# Mergen_Ground_Station_V2_0.net
KiCad netlist of a schematic drawn in EAGLE
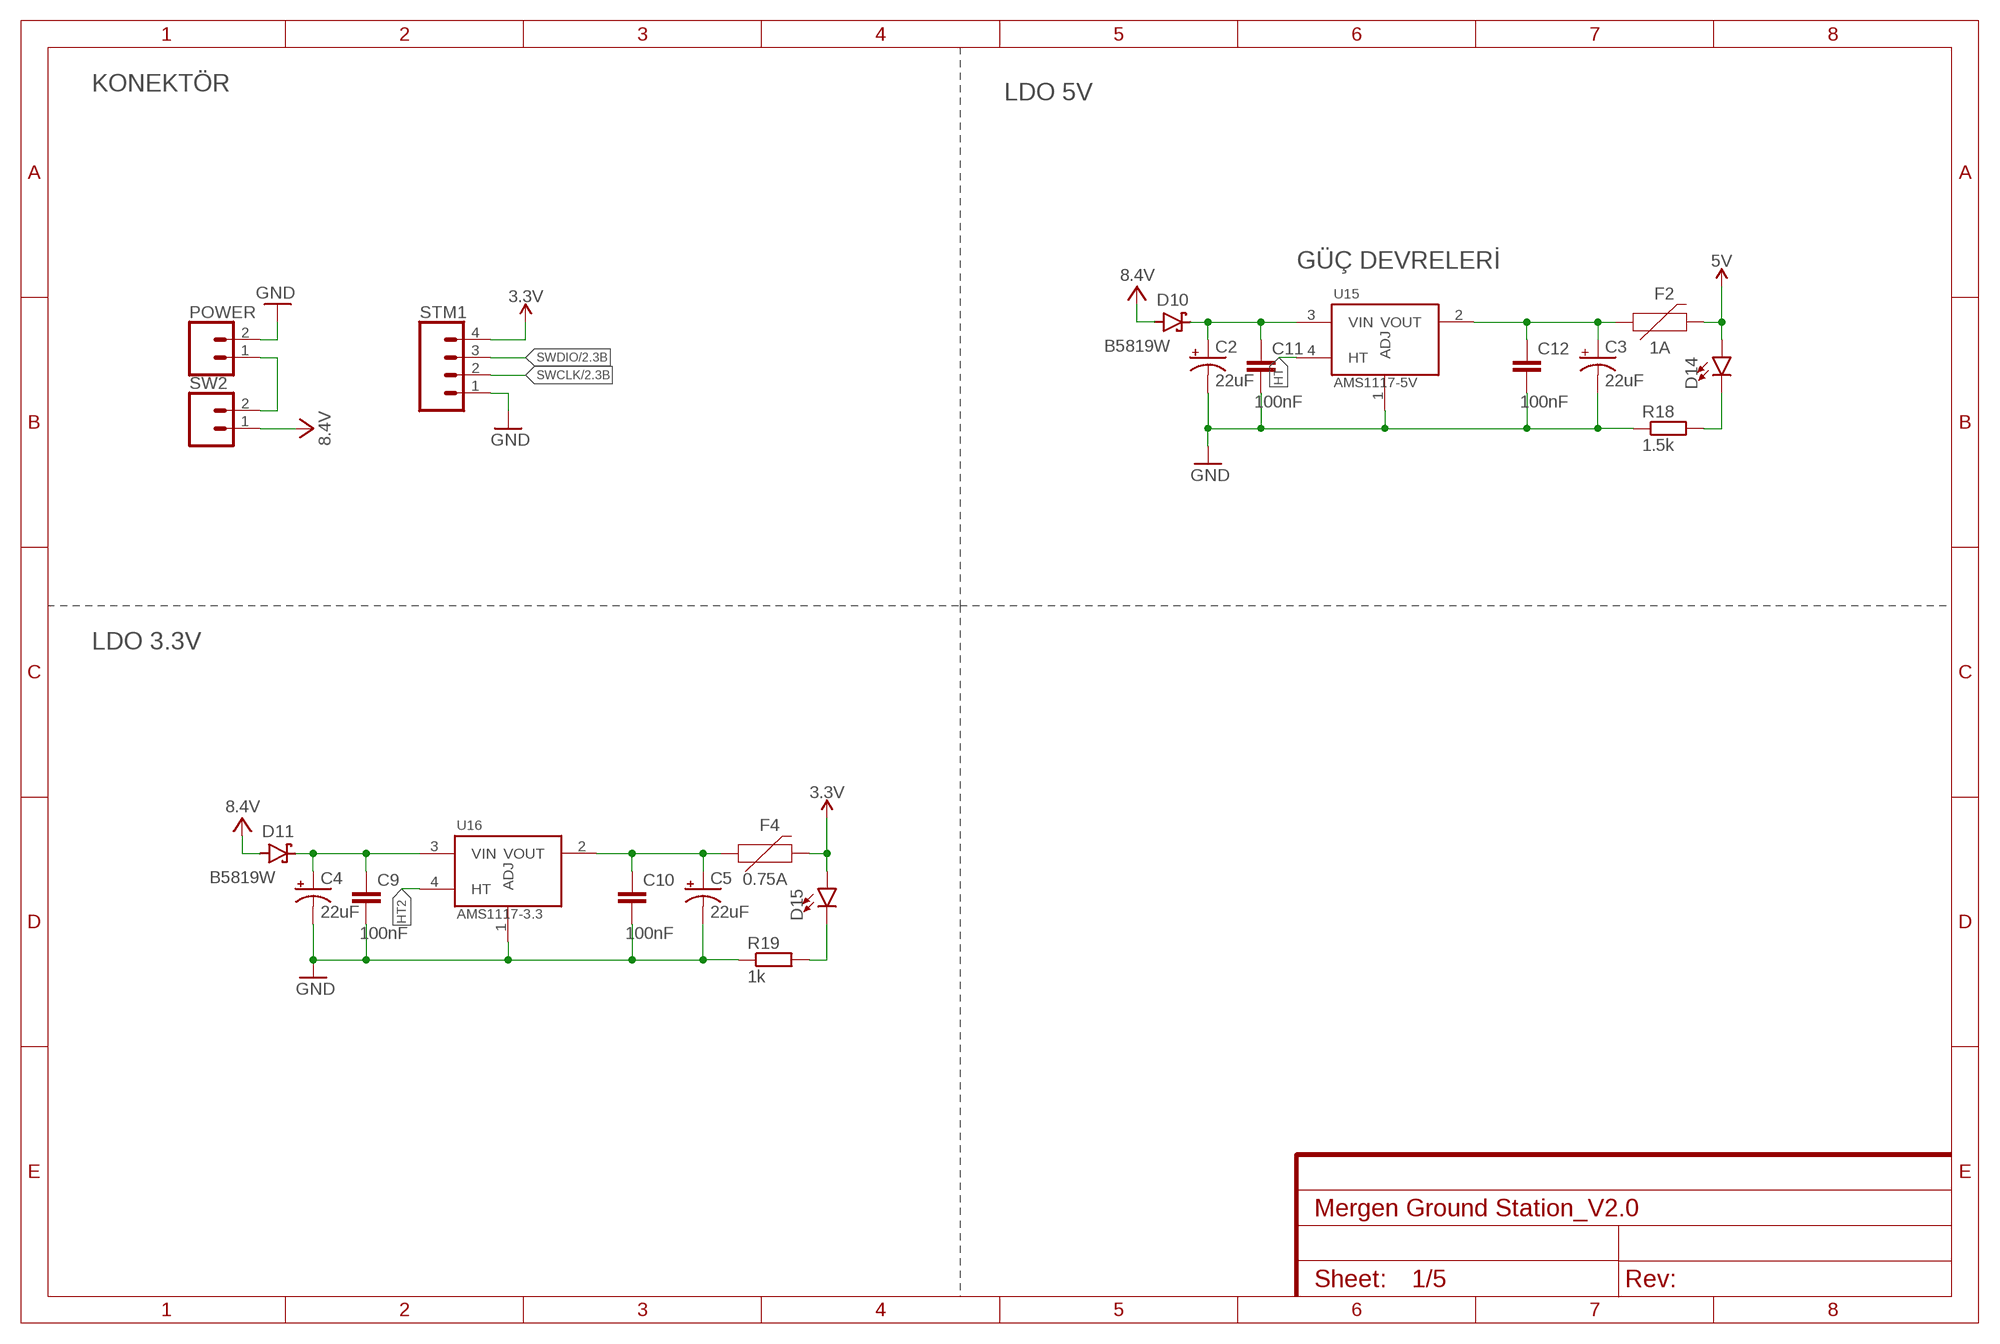
[diagram p0: schematic, sheet 1]
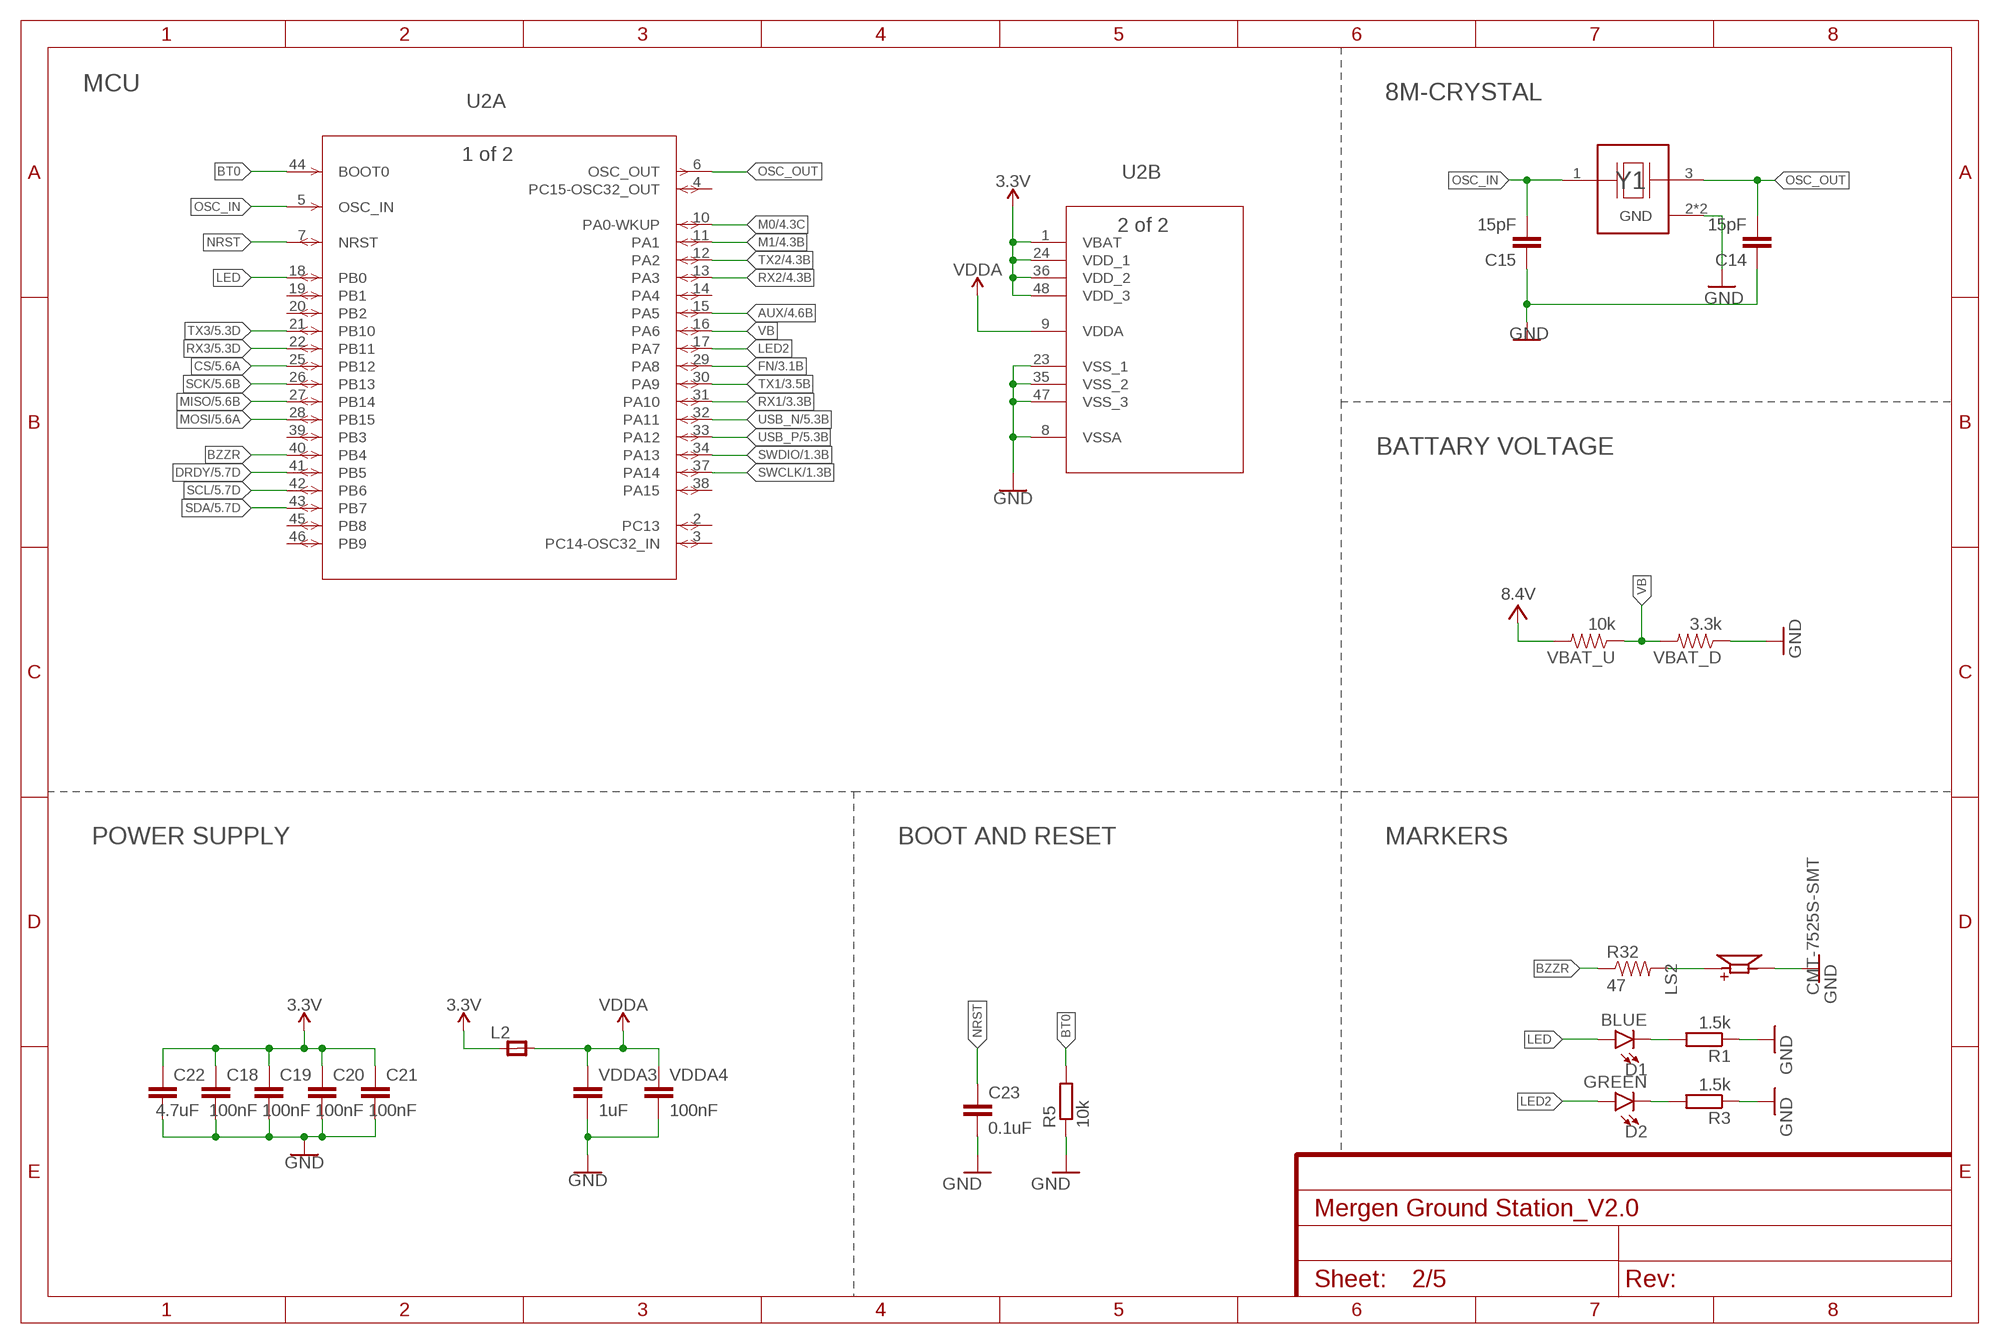
[diagram p1: schematic, sheet 2]
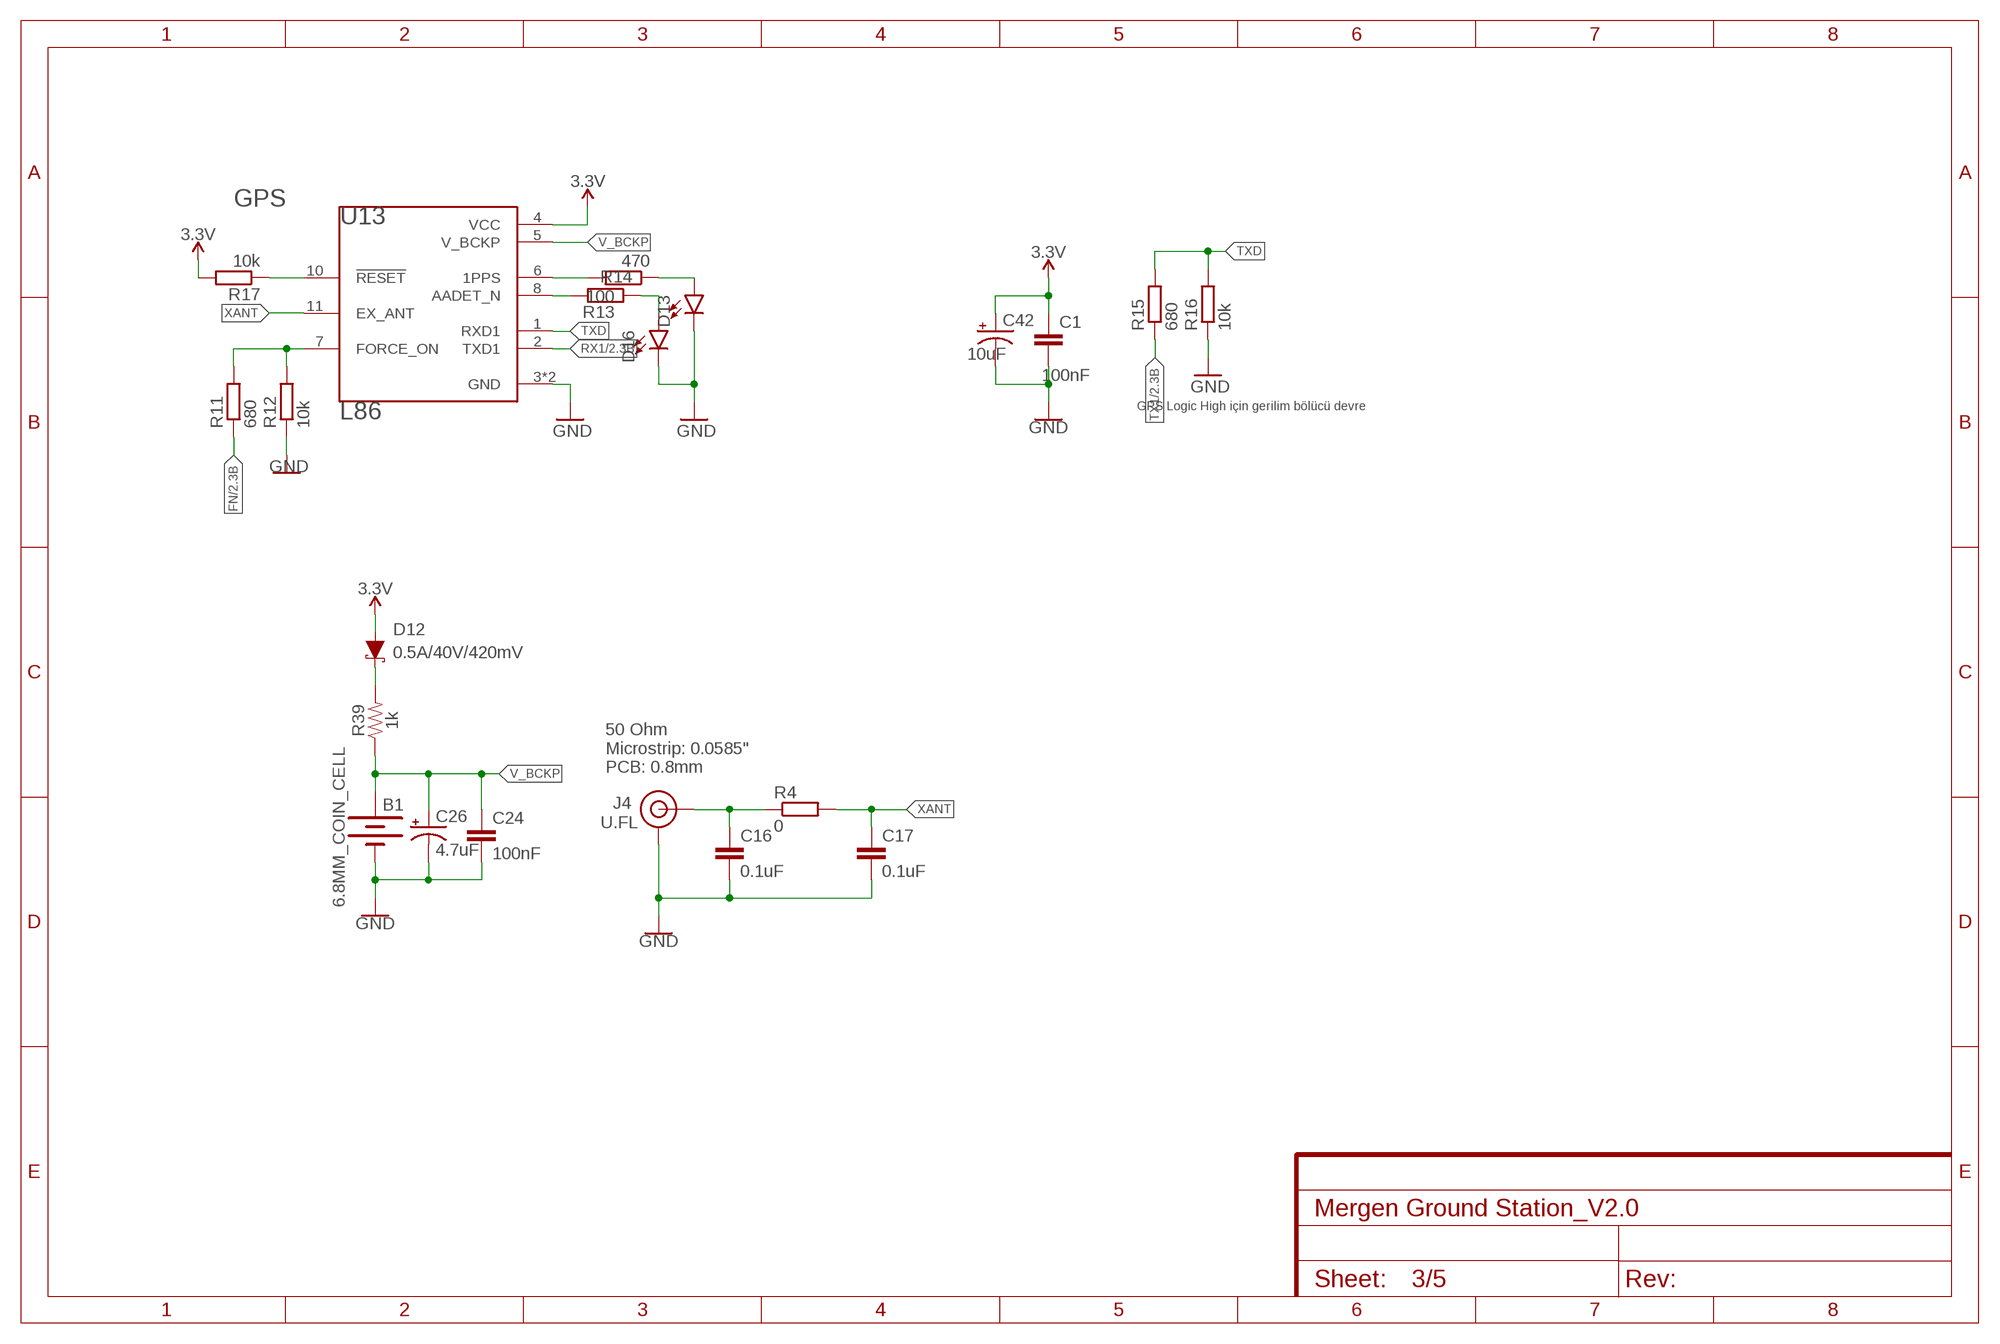
[diagram p2: schematic, sheet 3]
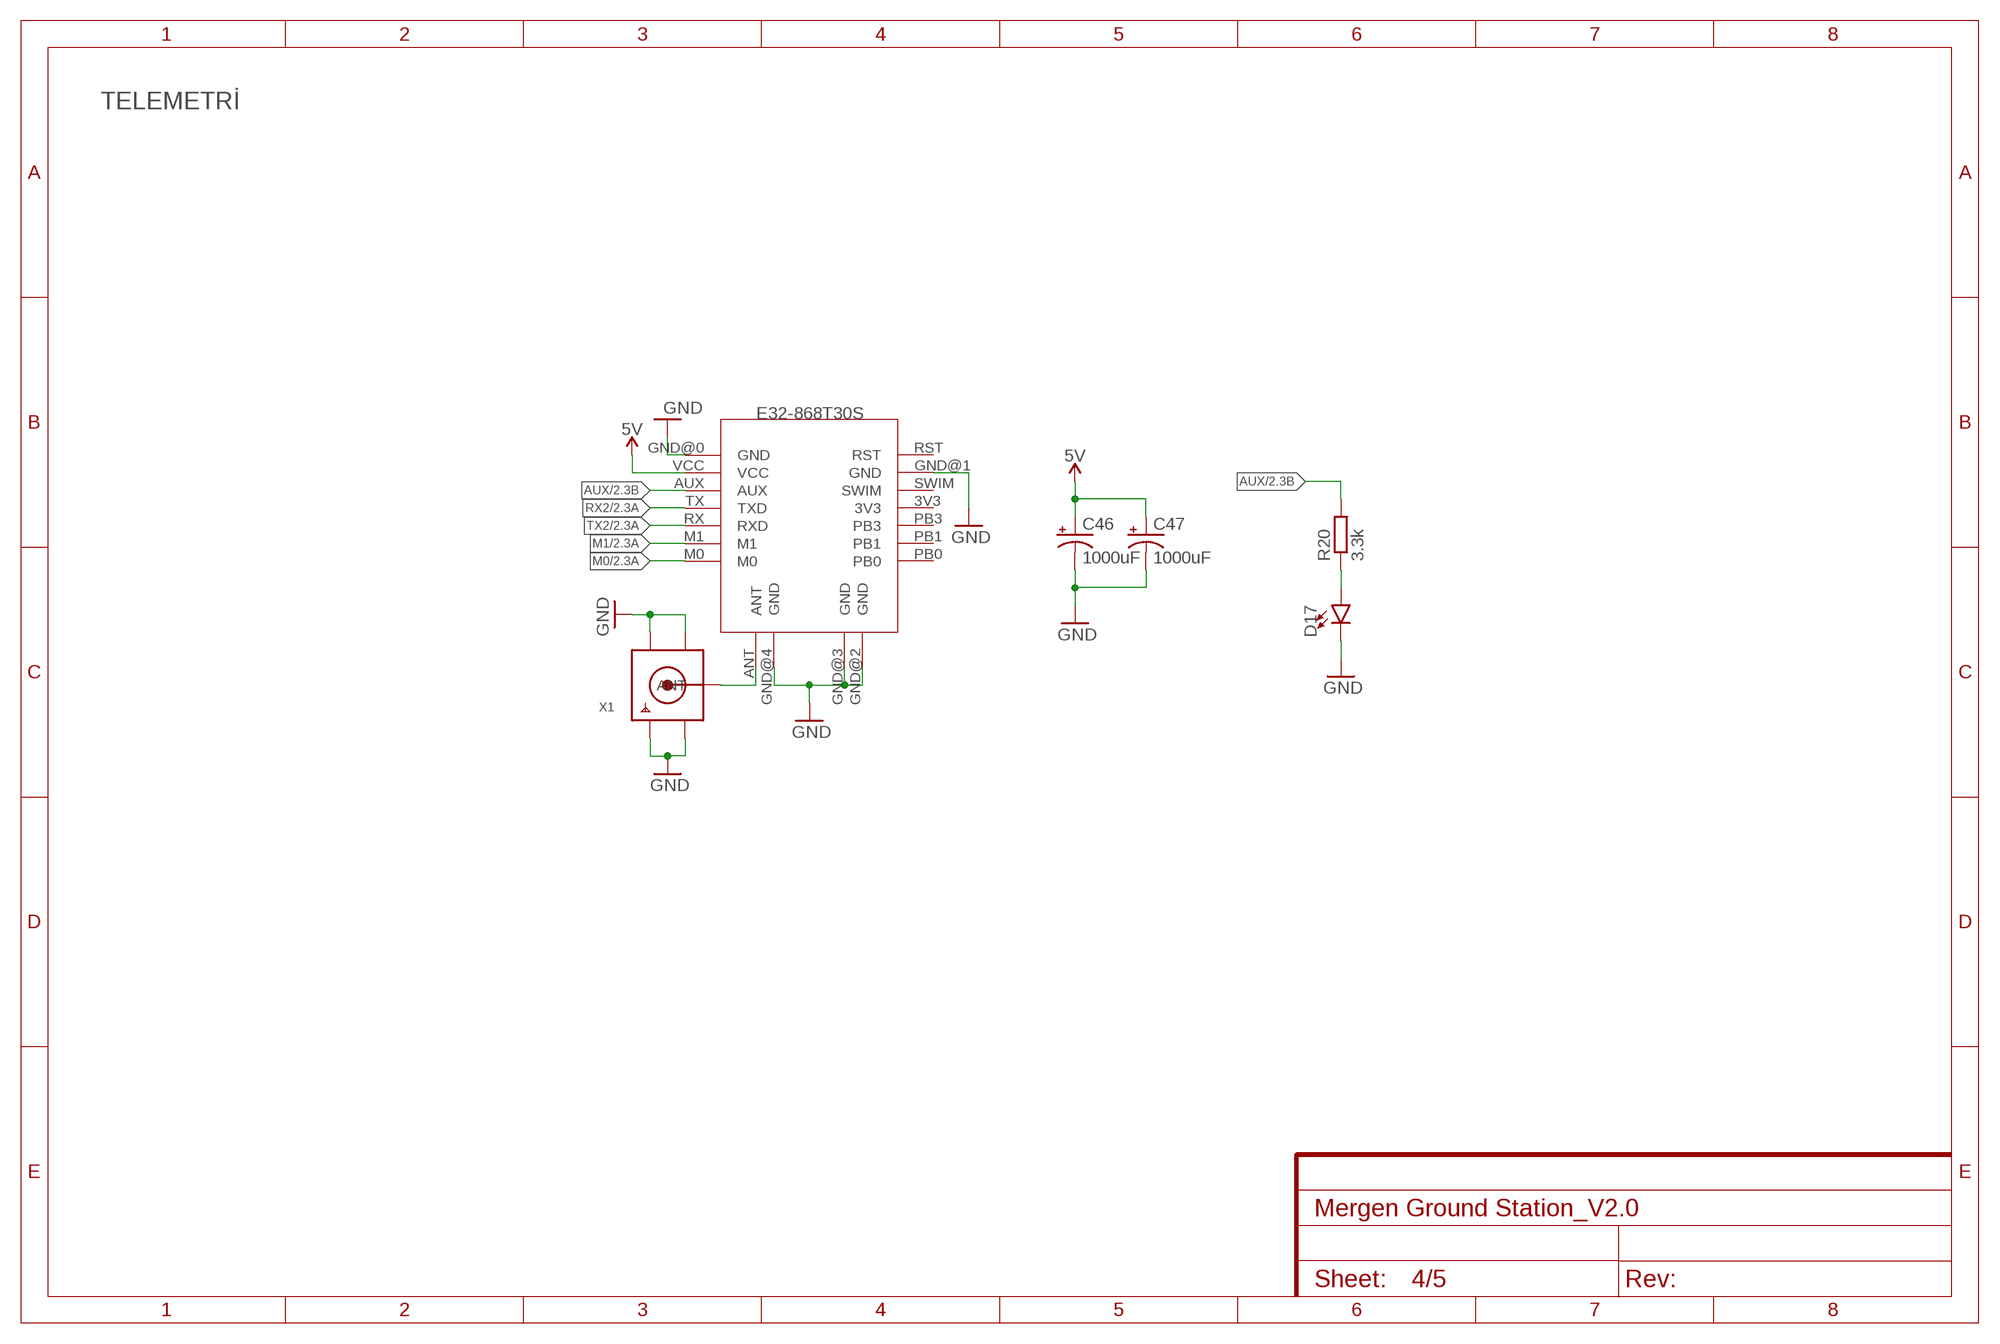
[diagram p3: schematic, sheet 4]
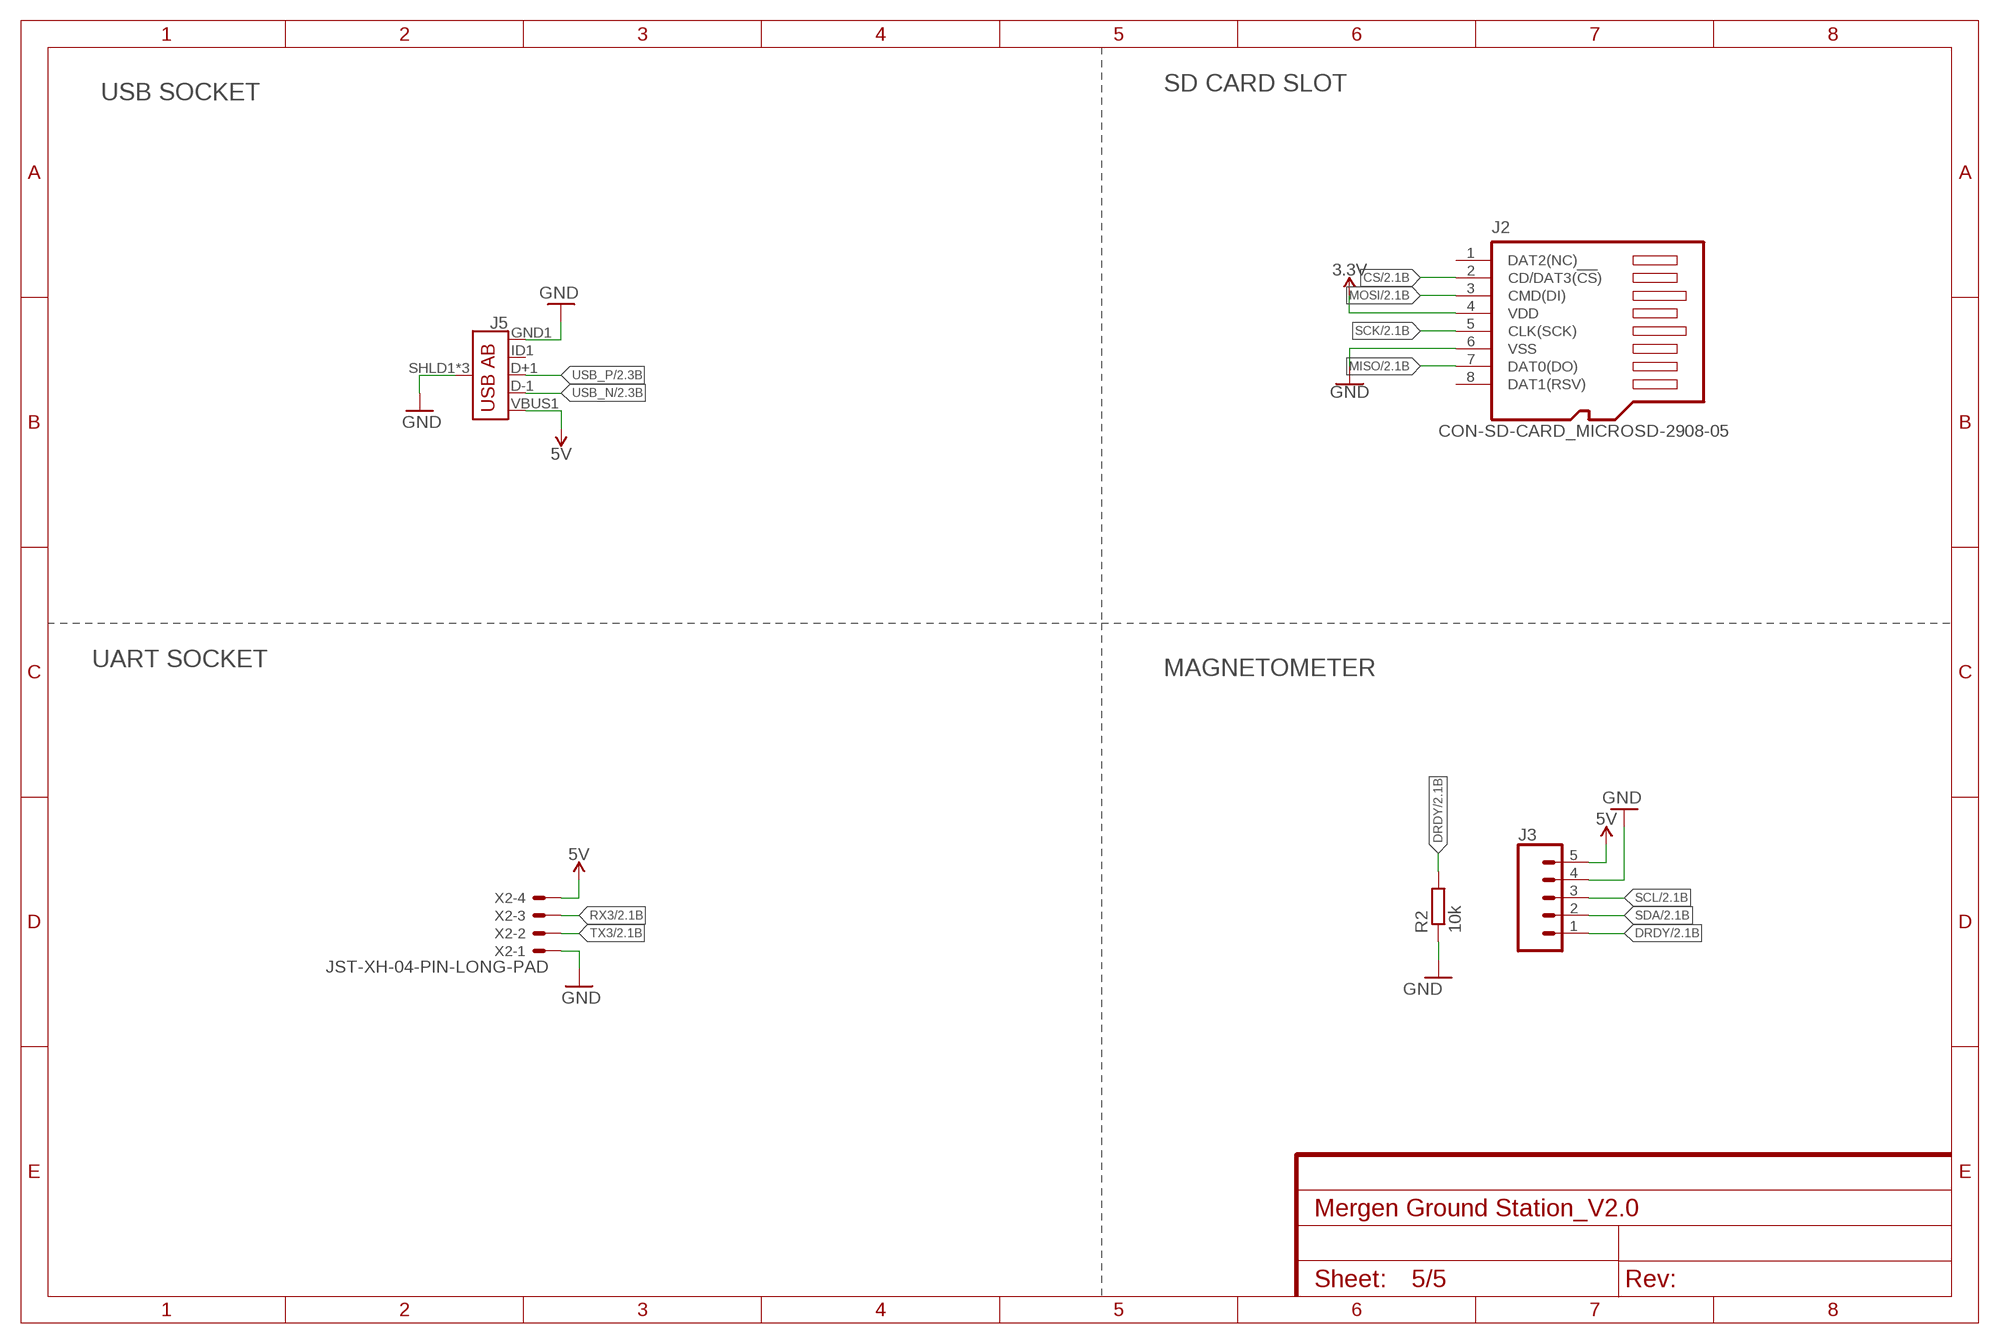
[diagram p4: schematic, sheet 5]

(export (version "E")
  (design (tool "Eeschema 10.0.6"))
  (components
    (comp (ref "B1")
      (value "6.8MM_COIN_CELL")
      (footprint "eagle-import:BATTCON-6.8MM")
      (libsource (lib "eagle-import") (part "BATTERY-6.8MM_SMD"))
    )
    (comp (ref "C1")
      (value "100nF")
      (footprint "eagle-import:C0603")
      (libsource (lib "eagle-import") (part "C-EUC0603"))
    )
    (comp (ref "C16")
      (value "0.1uF")
      (footprint "eagle-import:C0603")
      (libsource (lib "eagle-import") (part "C-EUC0603"))
    )
    (comp (ref "C17")
      (value "0.1uF")
      (footprint "eagle-import:C0603")
      (libsource (lib "eagle-import") (part "C-EUC0603"))
    )
    (comp (ref "C24")
      (value "100nF")
      (footprint "eagle-import:C0603")
      (libsource (lib "eagle-import") (part "C-EUC0603"))
    )
    (comp (ref "C26")
      (value "4.7uF")
      (footprint "eagle-import:A_3216-18R")
      (libsource (lib "eagle-import") (part "rcl_334_CPOL-USA/3216-18R"))
    )
    (comp (ref "C42")
      (value "10uF")
      (footprint "eagle-import:EIA3216")
      (libsource (lib "eagle-import") (part "10UF-POLAR-EIA3216-16V-10%(TANT)"))
    )
    (comp (ref "D12")
      (value "0.5A/40V/420mV")
      (footprint "eagle-import:SOD-323")
      (libsource (lib "eagle-import") (part "DIODE-SCHOTTKY-PMEG4005EJ"))
    )
    (comp (ref "D13")
      (value "LED0603")
      (footprint "eagle-import:LED-0603")
      (libsource (lib "eagle-import") (part "LED0603"))
    )
    (comp (ref "D16")
      (value "LED0603")
      (footprint "eagle-import:LED-0603")
      (libsource (lib "eagle-import") (part "LED0603"))
    )
    (comp (ref "J4")
      (value "U.FL")
      (footprint "eagle-import:U.FL")
      (libsource (lib "eagle-import") (part "U.FL2PIN"))
    )
    (comp (ref "R4")
      (value "0")
      (footprint "eagle-import:R0603")
      (libsource (lib "eagle-import") (part "R-EU_R0603"))
    )
    (comp (ref "R11")
      (value "680")
      (footprint "eagle-import:R0603")
      (libsource (lib "eagle-import") (part "R-EU_R0603"))
    )
    (comp (ref "R12")
      (value "10k")
      (footprint "eagle-import:R0603")
      (libsource (lib "eagle-import") (part "R-EU_R0603"))
    )
    (comp (ref "R13")
      (value "100")
      (footprint "eagle-import:R0603")
      (libsource (lib "eagle-import") (part "R-EU_R0603"))
    )
    (comp (ref "R14")
      (value "470")
      (footprint "eagle-import:R0603")
      (libsource (lib "eagle-import") (part "R-EU_R0603"))
    )
    (comp (ref "R15")
      (value "680")
      (footprint "eagle-import:R0603")
      (libsource (lib "eagle-import") (part "R-EU_R0603"))
    )
    (comp (ref "R16")
      (value "10k")
      (footprint "eagle-import:R0603")
      (libsource (lib "eagle-import") (part "R-EU_R0603"))
    )
    (comp (ref "R17")
      (value "10k")
      (footprint "eagle-import:R0603")
      (libsource (lib "eagle-import") (part "R-EU_R0603"))
    )
    (comp (ref "R39")
      (value "1k")
      (footprint "eagle-import:0603")
      (libsource (lib "eagle-import") (part "1KOHM-0603-1/10W-1%"))
    )
    (comp (ref "U13")
      (value "L86")
      (footprint "eagle-import:XCVR_L86")
      (fields (field (name "MF") "Quectel"))
      (libsource (lib "eagle-import") (part "L86"))
    )
    (comp (ref "C46")
      (value "1000uF")
      (footprint "eagle-import:150CLZ-1010")
      (libsource (lib "eagle-import") (part "CPOL-US150CLZ-1010"))
    )
    (comp (ref "C47")
      (value "1000uF")
      (footprint "eagle-import:150CLZ-1010")
      (libsource (lib "eagle-import") (part "CPOL-US150CLZ-1010"))
    )
    (comp (ref "D17")
      (value "LED0603")
      (footprint "eagle-import:LED-0603")
      (libsource (lib "eagle-import") (part "LED0603"))
    )
    (comp (ref "R20")
      (value "3.3k")
      (footprint "eagle-import:R0603")
      (libsource (lib "eagle-import") (part "R-EU_R0603"))
    )
    (comp (ref "U14")
      (value "E32-868T30S")
      (footprint "eagle-import:E32-868T30S")
      (libsource (lib "eagle-import") (part "E32-868T30S"))
    )
    (comp (ref "X1")
      (value "SMACONNECTOR")
      (footprint "eagle-import:SMA90_DIP")
      (libsource (lib "eagle-import") (part "SMACONNECTOR"))
    )
    (comp (ref "J2")
      (value "CON-SD-CARD_MICROSD-2908-05")
      (footprint "eagle-import:CON-SD-CARD_2908-05")
      (libsource (lib "eagle-import") (part "CON-SD-CARD_MICROSD-2908-05"))
    )
    (comp (ref "J3")
      (value "CONN_05LOCK_LONGPADS")
      (footprint "eagle-import:1X05_LOCK_LONGPADS")
      (libsource (lib "eagle-import") (part "CONN_05LOCK_LONGPADS"))
    )
    (comp (ref "J5")
      (value "USB_AB_SMT")
      (footprint "eagle-import:USB-AB-MICRO-SMD")
      (libsource (lib "eagle-import") (part "USB_AB_SMT"))
    )
    (comp (ref "R2")
      (value "10k")
      (footprint "eagle-import:R0603")
      (libsource (lib "eagle-import") (part "R-EU_R0603"))
    )
    (comp (ref "X2")
      (value "JST-XH-04-PIN-LONG-PAD")
      (footprint "eagle-import:JST-XH-04-PACKAGE-LONG-PAD")
      (libsource (lib "eagle-import") (part "JST-XH-04-PIN-LONG-PAD"))
    )
    (comp (ref "C2")
      (value "22uF")
      (footprint "eagle-import:CT3528")
      (libsource (lib "eagle-import") (part "rcl_334_CPOL-USCT3528"))
    )
    (comp (ref "C3")
      (value "22uF")
      (footprint "eagle-import:CT3528")
      (libsource (lib "eagle-import") (part "rcl_334_CPOL-USCT3528"))
    )
    (comp (ref "C4")
      (value "22uF")
      (footprint "eagle-import:CT3528")
      (libsource (lib "eagle-import") (part "rcl_334_CPOL-USCT3528"))
    )
    (comp (ref "C5")
      (value "22uF")
      (footprint "eagle-import:CT3528")
      (libsource (lib "eagle-import") (part "rcl_334_CPOL-USCT3528"))
    )
    (comp (ref "C9")
      (value "100nF")
      (footprint "eagle-import:C0603")
      (libsource (lib "eagle-import") (part "C-EUC0603"))
    )
    (comp (ref "C10")
      (value "100nF")
      (footprint "eagle-import:C0603")
      (libsource (lib "eagle-import") (part "C-EUC0603"))
    )
    (comp (ref "C11")
      (value "100nF")
      (footprint "eagle-import:C0603")
      (libsource (lib "eagle-import") (part "C-EUC0603"))
    )
    (comp (ref "C12")
      (value "100nF")
      (footprint "eagle-import:C0603")
      (libsource (lib "eagle-import") (part "C-EUC0603"))
    )
    (comp (ref "D10")
      (value "B5819W")
      (footprint "eagle-import:SODFL3718X115")
      (fields (field (name "MANUFACTURER") "ON Semiconductor") (field (name "MPN") "MBR0520LT1G"))
      (libsource (lib "eagle-import") (part "SCHOTTKY_DO-219MBR0520LT1G"))
    )
    (comp (ref "D11")
      (value "B5819W")
      (footprint "eagle-import:SODFL3718X115")
      (fields (field (name "MANUFACTURER") "ON Semiconductor") (field (name "MPN") "MBR0520LT1G"))
      (libsource (lib "eagle-import") (part "SCHOTTKY_DO-219MBR0520LT1G"))
    )
    (comp (ref "D14")
      (value "LED0603")
      (footprint "eagle-import:LED-0603")
      (libsource (lib "eagle-import") (part "LED0603"))
    )
    (comp (ref "D15")
      (value "LED0603")
      (footprint "eagle-import:LED-0603")
      (libsource (lib "eagle-import") (part "LED0603"))
    )
    (comp (ref "F2")
      (value "1A")
      (footprint "eagle-import:1206")
      (libsource (lib "eagle-import") (part "PPTC_HALF-AMP"))
    )
    (comp (ref "F4")
      (value "0.75A")
      (footprint "eagle-import:1206")
      (libsource (lib "eagle-import") (part "PPTC_HALF-AMP"))
    )
    (comp (ref "POWER")
      (value "CONN_023.5MM-NO_SILK")
      (footprint "eagle-import:SCREWTERMINAL-3.5MM-2-NS")
      (libsource (lib "eagle-import") (part "CONN_023.5MM-NO_SILK"))
    )
    (comp (ref "R18")
      (value "1.5k")
      (footprint "eagle-import:R0603")
      (libsource (lib "eagle-import") (part "R-EU_R0603"))
    )
    (comp (ref "R19")
      (value "1k")
      (footprint "eagle-import:R0603")
      (libsource (lib "eagle-import") (part "R-EU_R0603"))
    )
    (comp (ref "STM1")
      (value "CONN_04")
      (footprint "eagle-import:1X04")
      (libsource (lib "eagle-import") (part "CONN_04"))
    )
    (comp (ref "SW2")
      (value "CONN_023.5MM-NO_SILK")
      (footprint "eagle-import:SCREWTERMINAL-3.5MM-2-NS")
      (libsource (lib "eagle-import") (part "CONN_023.5MM-NO_SILK"))
    )
    (comp (ref "U15")
      (value "AMS1117-5V")
      (footprint "eagle-import:SOT229P700X180-4N")
      (fields (field (name "MF") "Advanced Monolithic Systems") (field (name "MP") "AMS1117-3.3"))
      (libsource (lib "eagle-import") (part "AMS1117-3.3"))
    )
    (comp (ref "U16")
      (value "AMS1117-3.3")
      (footprint "eagle-import:SOT229P700X180-4N")
      (fields (field (name "MF") "Advanced Monolithic Systems"))
      (libsource (lib "eagle-import") (part "AMS1117-3.3"))
    )
    (comp (ref "C14")
      (value "15pF")
      (footprint "eagle-import:C0603")
      (libsource (lib "eagle-import") (part "C-EUC0603"))
    )
    (comp (ref "C15")
      (value "15pF")
      (footprint "eagle-import:C0603")
      (libsource (lib "eagle-import") (part "C-EUC0603"))
    )
    (comp (ref "C18")
      (value "100nF")
      (footprint "eagle-import:C0603")
      (libsource (lib "eagle-import") (part "C-EUC0603"))
    )
    (comp (ref "C19")
      (value "100nF")
      (footprint "eagle-import:C0603")
      (libsource (lib "eagle-import") (part "C-EUC0603"))
    )
    (comp (ref "C20")
      (value "100nF")
      (footprint "eagle-import:C0603")
      (libsource (lib "eagle-import") (part "C-EUC0603"))
    )
    (comp (ref "C21")
      (value "100nF")
      (footprint "eagle-import:C0603")
      (libsource (lib "eagle-import") (part "C-EUC0603"))
    )
    (comp (ref "C22")
      (value "4.7uF")
      (footprint "eagle-import:C0603")
      (libsource (lib "eagle-import") (part "C-EUC0603"))
    )
    (comp (ref "C23")
      (value "0.1uF")
      (footprint "eagle-import:C0603")
      (libsource (lib "eagle-import") (part "C-EUC0603"))
    )
    (comp (ref "D1")
      (value "BLUE")
      (footprint "eagle-import:LED-0603")
      (libsource (lib "eagle-import") (part "LED0603"))
    )
    (comp (ref "D2")
      (value "GREEN")
      (footprint "eagle-import:LED-0603")
      (libsource (lib "eagle-import") (part "LED0603"))
    )
    (comp (ref "L2")
      (value "RC-MASTER-SMD_FB_0805MP")
      (footprint "eagle-import:RC-MASTER-SMD_L0805MP")
      (libsource (lib "eagle-import") (part "RC-MASTER-SMD_FB_0805MP"))
    )
    (comp (ref "LS2")
      (value "CMT-7525S-SMT")
      (footprint "eagle-import:CUI_CMT-7525S-SMT")
      (fields (field (name "MF") "CUI Devices") (field (name "MP") "CMT-7525S-SMT-TR"))
      (libsource (lib "eagle-import") (part "CMT-7525S-SMT"))
    )
    (comp (ref "R1")
      (value "1.5k")
      (footprint "eagle-import:R0603")
      (libsource (lib "eagle-import") (part "R-EU_R0603"))
    )
    (comp (ref "R3")
      (value "1.5k")
      (footprint "eagle-import:R0603")
      (libsource (lib "eagle-import") (part "R-EU_R0603"))
    )
    (comp (ref "R5")
      (value "10k")
      (footprint "eagle-import:R0603")
      (libsource (lib "eagle-import") (part "R-EU_R0603"))
    )
    (comp (ref "R32")
      (value "47")
      (footprint "eagle-import:0603")
      (libsource (lib "eagle-import") (part "0OHM-0603-1/10W-5%"))
    )
    (comp (ref "U2")
      (value "STM32F103C8T6")
      (footprint "eagle-import:LQFP48-7X7MM")
      (fields (field (name "COPYRIGHT") "Copyright (C) 2018 Accelerated Designs. All rights reserved"))
      (libsource (lib "eagle-import") (part "STM32F103C8T6"))
    )
    (comp (ref "VBAT_D")
      (value "3.3k")
      (footprint "eagle-import:0603-RES")
      (libsource (lib "eagle-import") (part "2.0KOHM1/10W5%(0603)"))
    )
    (comp (ref "VBAT_U")
      (value "10k")
      (footprint "eagle-import:0603-RES")
      (libsource (lib "eagle-import") (part "2.0KOHM1/10W5%(0603)"))
    )
    (comp (ref "VDDA3")
      (value "1uF")
      (footprint "eagle-import:0603")
      (libsource (lib "eagle-import") (part "0.1UF-0603-25V-(+80/-20%)"))
    )
    (comp (ref "VDDA4")
      (value "100nF")
      (footprint "eagle-import:0603")
      (libsource (lib "eagle-import") (part "0.1UF-0603-25V-(+80/-20%)"))
    )
    (comp (ref "Y1")
      (value "ABMM2-8.000MHZ-E2-T")
      (footprint "eagle-import:XTAL_ABMM2-8.000MHZ-E2-T")
      (fields (field (name "MF") "Abracon"))
      (libsource (lib "eagle-import") (part "ABMM2-8.000MHZ-E2-T"))
    )
  )
  (nets
    (net (code "1") (name "3.3V") (class "Default")
      (node (ref "C1") (pin "1") (pinfunction "1_1") (pintype "passive"))
      (node (ref "C18") (pin "1") (pinfunction "1_1") (pintype "passive"))
      (node (ref "C19") (pin "1") (pinfunction "1_1") (pintype "passive"))
      (node (ref "C20") (pin "1") (pinfunction "1_1") (pintype "passive"))
      (node (ref "C21") (pin "1") (pinfunction "1_1") (pintype "passive"))
      (node (ref "C22") (pin "1") (pinfunction "1_1") (pintype "passive"))
      (node (ref "C42") (pin "+") (pinfunction "+_+") (pintype "passive"))
      (node (ref "D12") (pin "A") (pinfunction "A_A") (pintype "passive"))
      (node (ref "D15") (pin "A") (pinfunction "A_A") (pintype "passive"))
      (node (ref "F4") (pin "2") (pinfunction "2_2") (pintype "bidirectional"))
      (node (ref "J2") (pin "4") (pinfunction "VDD_4") (pintype "bidirectional"))
      (node (ref "L2") (pin "1") (pinfunction "1_1") (pintype "passive"))
      (node (ref "R17") (pin "2") (pinfunction "2_2") (pintype "passive"))
      (node (ref "STM1") (pin "4") (pinfunction "4_4") (pintype "passive"))
      (node (ref "U13") (pin "4") (pinfunction "VCC_4") (pintype "power_in"))
      (node (ref "U2") (pin "1") (pinfunction "VBAT_1") (pintype "power_in"))
      (node (ref "U2") (pin "24") (pinfunction "VDD_1_24") (pintype "power_in"))
      (node (ref "U2") (pin "36") (pinfunction "VDD_2_36") (pintype "power_in"))
      (node (ref "U2") (pin "48") (pinfunction "VDD_3_48") (pintype "power_in"))
    )
    (net (code "2") (name "5V") (class "Default")
      (node (ref "C46") (pin "+") (pinfunction "+_+") (pintype "passive"))
      (node (ref "C47") (pin "+") (pinfunction "+_+") (pintype "passive"))
      (node (ref "D14") (pin "A") (pinfunction "A_A") (pintype "passive"))
      (node (ref "F2") (pin "2") (pinfunction "2_2") (pintype "bidirectional"))
      (node (ref "J3") (pin "5") (pinfunction "5_5") (pintype "passive"))
      (node (ref "J5") (pin "VBUS1") (pinfunction "VBUS_VBUS1") (pintype "power_in"))
      (node (ref "U14") (pin "VCC") (pinfunction "VCC_VCC") (pintype "bidirectional"))
      (node (ref "X2") (pin "4") (pinfunction "S_4") (pintype "passive"))
    )
    (net (code "3") (name "AUX") (class "Default")
      (node (ref "R20") (pin "2") (pinfunction "2_2") (pintype "passive"))
      (node (ref "U14") (pin "AUX") (pinfunction "AUX_AUX") (pintype "bidirectional"))
      (node (ref "U2") (pin "15") (pinfunction "PA5_15") (pintype "bidirectional"))
    )
    (net (code "4") (name "BT0") (class "Default")
      (node (ref "R5") (pin "2") (pinfunction "2_2") (pintype "passive"))
      (node (ref "U2") (pin "44") (pinfunction "BOOT0_44") (pintype "input"))
    )
    (net (code "5") (name "BZZR") (class "Default")
      (node (ref "R32") (pin "1") (pinfunction "1_1") (pintype "passive"))
      (node (ref "U2") (pin "40") (pinfunction "PB4_40") (pintype "bidirectional"))
    )
    (net (code "6") (name "CS") (class "Default")
      (node (ref "J2") (pin "2") (pinfunction "CD/DAT3(~{CS})_2") (pintype "bidirectional"))
      (node (ref "U2") (pin "25") (pinfunction "PB12_25") (pintype "bidirectional"))
    )
    (net (code "7") (name "DRDY") (class "Default")
      (node (ref "J3") (pin "1") (pinfunction "1_1") (pintype "passive"))
      (node (ref "R2") (pin "2") (pinfunction "2_2") (pintype "passive"))
      (node (ref "U2") (pin "41") (pinfunction "PB5_41") (pintype "bidirectional"))
    )
    (net (code "8") (name "FN") (class "Default")
      (node (ref "R11") (pin "1") (pinfunction "1_1") (pintype "passive"))
      (node (ref "U2") (pin "29") (pinfunction "PA8_29") (pintype "bidirectional"))
    )
    (net (code "9") (name "GND") (class "Default")
      (node (ref "B1") (pin "-") (pinfunction "-_-") (pintype "power_in"))
      (node (ref "C1") (pin "2") (pinfunction "2_2") (pintype "passive"))
      (node (ref "C10") (pin "2") (pinfunction "2_2") (pintype "passive"))
      (node (ref "C11") (pin "2") (pinfunction "2_2") (pintype "passive"))
      (node (ref "C12") (pin "2") (pinfunction "2_2") (pintype "passive"))
      (node (ref "C14") (pin "1") (pinfunction "1_1") (pintype "passive"))
      (node (ref "C15") (pin "1") (pinfunction "1_1") (pintype "passive"))
      (node (ref "C16") (pin "2") (pinfunction "2_2") (pintype "passive"))
      (node (ref "C17") (pin "2") (pinfunction "2_2") (pintype "passive"))
      (node (ref "C18") (pin "2") (pinfunction "2_2") (pintype "passive"))
      (node (ref "C19") (pin "2") (pinfunction "2_2") (pintype "passive"))
      (node (ref "C2") (pin "-") (pinfunction "-_-") (pintype "passive"))
      (node (ref "C20") (pin "2") (pinfunction "2_2") (pintype "passive"))
      (node (ref "C21") (pin "2") (pinfunction "2_2") (pintype "passive"))
      (node (ref "C22") (pin "2") (pinfunction "2_2") (pintype "passive"))
      (node (ref "C23") (pin "2") (pinfunction "2_2") (pintype "passive"))
      (node (ref "C24") (pin "2") (pinfunction "2_2") (pintype "passive"))
      (node (ref "C26") (pin "-") (pinfunction "-_-") (pintype "passive"))
      (node (ref "C3") (pin "-") (pinfunction "-_-") (pintype "passive"))
      (node (ref "C4") (pin "-") (pinfunction "-_-") (pintype "passive"))
      (node (ref "C42") (pin "-") (pinfunction "-_-") (pintype "passive"))
      (node (ref "C46") (pin "-") (pinfunction "-_-") (pintype "passive"))
      (node (ref "C47") (pin "-") (pinfunction "-_-") (pintype "passive"))
      (node (ref "C5") (pin "-") (pinfunction "-_-") (pintype "passive"))
      (node (ref "C9") (pin "2") (pinfunction "2_2") (pintype "passive"))
      (node (ref "D13") (pin "C") (pinfunction "C_C") (pintype "passive"))
      (node (ref "D16") (pin "C") (pinfunction "C_C") (pintype "passive"))
      (node (ref "D17") (pin "C") (pinfunction "C_C") (pintype "passive"))
      (node (ref "J2") (pin "6") (pinfunction "VSS_6") (pintype "bidirectional"))
      (node (ref "J3") (pin "4") (pinfunction "4_4") (pintype "passive"))
      (node (ref "J4") (pin "1") (pinfunction "GND_1") (pintype "bidirectional"))
      (node (ref "J4") (pin "2") (pinfunction "GND_2") (pintype "bidirectional"))
      (node (ref "J5") (pin "GND1") (pinfunction "GND_GND1") (pintype "power_in"))
      (node (ref "J5") (pin "SHLD1") (pinfunction "SHIELD_SHLD1") (pintype "bidirectional"))
      (node (ref "J5") (pin "SHLD2") (pinfunction "SHIELD_SHLD2") (pintype "bidirectional"))
      (node (ref "J5") (pin "SHLD3") (pinfunction "SHIELD_SHLD3") (pintype "bidirectional"))
      (node (ref "LS2") (pin "N") (pinfunction "N_N") (pintype "passive"))
      (node (ref "POWER") (pin "2") (pinfunction "2_2") (pintype "passive"))
      (node (ref "R1") (pin "1") (pinfunction "1_1") (pintype "passive"))
      (node (ref "R12") (pin "1") (pinfunction "1_1") (pintype "passive"))
      (node (ref "R16") (pin "1") (pinfunction "1_1") (pintype "passive"))
      (node (ref "R18") (pin "1") (pinfunction "1_1") (pintype "passive"))
      (node (ref "R19") (pin "1") (pinfunction "1_1") (pintype "passive"))
      (node (ref "R2") (pin "1") (pinfunction "1_1") (pintype "passive"))
      (node (ref "R3") (pin "1") (pinfunction "1_1") (pintype "passive"))
      (node (ref "R5") (pin "1") (pinfunction "1_1") (pintype "passive"))
      (node (ref "STM1") (pin "1") (pinfunction "1_1") (pintype "passive"))
      (node (ref "U13") (pin "12") (pinfunction "GND_12") (pintype "passive"))
      (node (ref "U13") (pin "3") (pinfunction "GND_3") (pintype "passive"))
      (node (ref "U14") (pin "GND@0") (pinfunction "GND_GND@0") (pintype "bidirectional"))
      (node (ref "U14") (pin "GND@1") (pinfunction "GND_GND@1") (pintype "bidirectional"))
      (node (ref "U14") (pin "GND@2") (pinfunction "GND_GND@2") (pintype "bidirectional"))
      (node (ref "U14") (pin "GND@3") (pinfunction "GND_GND@3") (pintype "bidirectional"))
      (node (ref "U14") (pin "GND@4") (pinfunction "GND_GND@4") (pintype "bidirectional"))
      (node (ref "U15") (pin "1") (pinfunction "ADJ_1") (pintype "power_in"))
      (node (ref "U16") (pin "1") (pinfunction "ADJ_1") (pintype "power_in"))
      (node (ref "U2") (pin "23") (pinfunction "VSS_1_23") (pintype "power_in"))
      (node (ref "U2") (pin "35") (pinfunction "VSS_2_35") (pintype "power_in"))
      (node (ref "U2") (pin "47") (pinfunction "VSS_3_47") (pintype "power_in"))
      (node (ref "U2") (pin "8") (pinfunction "VSSA_8") (pintype "power_in"))
      (node (ref "VBAT_D") (pin "1") (pinfunction "1_1") (pintype "passive"))
      (node (ref "VDDA3") (pin "2") (pinfunction "2_2") (pintype "passive"))
      (node (ref "VDDA4") (pin "2") (pinfunction "2_2") (pintype "passive"))
      (node (ref "X1") (pin "GND1") (pinfunction "GND1_GND1") (pintype "power_in"))
      (node (ref "X1") (pin "GND2") (pinfunction "GND2_GND2") (pintype "power_in"))
      (node (ref "X1") (pin "GND3") (pinfunction "GND3_GND3") (pintype "power_in"))
      (node (ref "X1") (pin "GND4") (pinfunction "GND4_GND4") (pintype "power_in"))
      (node (ref "X2") (pin "1") (pinfunction "S_1") (pintype "passive"))
      (node (ref "Y1") (pin "2") (pinfunction "GND_2") (pintype "power_in"))
      (node (ref "Y1") (pin "4") (pinfunction "GND_4") (pintype "power_in"))
    )
    (net (code "10") (name "HT") (class "Default")
      (node (ref "U15") (pin "4") (pinfunction "HT_4") (pintype "bidirectional"))
    )
    (net (code "11") (name "HT2") (class "Default")
      (node (ref "U16") (pin "4") (pinfunction "HT_4") (pintype "bidirectional"))
    )
    (net (code "12") (name "LED") (class "Default")
      (node (ref "D1") (pin "A") (pinfunction "A_A") (pintype "passive"))
      (node (ref "U2") (pin "18") (pinfunction "PB0_18") (pintype "bidirectional"))
    )
    (net (code "13") (name "LED2") (class "Default")
      (node (ref "D2") (pin "A") (pinfunction "A_A") (pintype "passive"))
      (node (ref "U2") (pin "17") (pinfunction "PA7_17") (pintype "bidirectional"))
    )
    (net (code "14") (name "M0") (class "Default")
      (node (ref "U14") (pin "M0") (pinfunction "M0_M0") (pintype "bidirectional"))
      (node (ref "U2") (pin "10") (pinfunction "PA0-WKUP_10") (pintype "bidirectional"))
    )
    (net (code "15") (name "M1") (class "Default")
      (node (ref "U14") (pin "M1") (pinfunction "M1_M1") (pintype "bidirectional"))
      (node (ref "U2") (pin "11") (pinfunction "PA1_11") (pintype "bidirectional"))
    )
    (net (code "16") (name "MISO") (class "Default")
      (node (ref "J2") (pin "7") (pinfunction "DAT0(DO)_7") (pintype "bidirectional"))
      (node (ref "U2") (pin "27") (pinfunction "PB14_27") (pintype "bidirectional"))
    )
    (net (code "17") (name "MOSI") (class "Default")
      (node (ref "J2") (pin "3") (pinfunction "CMD(DI)_3") (pintype "bidirectional"))
      (node (ref "U2") (pin "28") (pinfunction "PB15_28") (pintype "bidirectional"))
    )
    (net (code "18") (name "NRST") (class "Default")
      (node (ref "C23") (pin "1") (pinfunction "1_1") (pintype "passive"))
      (node (ref "U2") (pin "7") (pinfunction "NRST_7") (pintype "bidirectional"))
    )
    (net (code "19") (name "Net-(D1-PadC)") (class "Default")
      (node (ref "D1") (pin "C") (pinfunction "C_C") (pintype "passive"))
      (node (ref "R1") (pin "2") (pinfunction "2_2") (pintype "passive"))
    )
    (net (code "20") (name "Net-(D2-PadC)") (class "Default")
      (node (ref "D2") (pin "C") (pinfunction "C_C") (pintype "passive"))
      (node (ref "R3") (pin "2") (pinfunction "2_2") (pintype "passive"))
    )
    (net (code "21") (name "Net-(D10-C)") (class "Default")
      (node (ref "C11") (pin "1") (pinfunction "1_1") (pintype "passive"))
      (node (ref "C2") (pin "+") (pinfunction "+_+") (pintype "passive"))
      (node (ref "D10") (pin "1") (pinfunction "C_1") (pintype "passive"))
      (node (ref "U15") (pin "3") (pinfunction "VIN_3") (pintype "input"))
    )
    (net (code "22") (name "Net-(D11-C)") (class "Default")
      (node (ref "C4") (pin "+") (pinfunction "+_+") (pintype "passive"))
      (node (ref "C9") (pin "1") (pinfunction "1_1") (pintype "passive"))
      (node (ref "D11") (pin "1") (pinfunction "C_1") (pintype "passive"))
      (node (ref "U16") (pin "3") (pinfunction "VIN_3") (pintype "input"))
    )
    (net (code "23") (name "Net-(D12-PadC)") (class "Default")
      (node (ref "D12") (pin "C") (pinfunction "C_C") (pintype "passive"))
      (node (ref "R39") (pin "2") (pinfunction "2_2") (pintype "passive"))
    )
    (net (code "24") (name "Net-(D13-PadA)") (class "Default")
      (node (ref "D13") (pin "A") (pinfunction "A_A") (pintype "passive"))
      (node (ref "R14") (pin "1") (pinfunction "1_1") (pintype "passive"))
    )
    (net (code "25") (name "Net-(D14-PadC)") (class "Default")
      (node (ref "D14") (pin "C") (pinfunction "C_C") (pintype "passive"))
      (node (ref "R18") (pin "2") (pinfunction "2_2") (pintype "passive"))
    )
    (net (code "26") (name "Net-(D15-PadC)") (class "Default")
      (node (ref "D15") (pin "C") (pinfunction "C_C") (pintype "passive"))
      (node (ref "R19") (pin "2") (pinfunction "2_2") (pintype "passive"))
    )
    (net (code "27") (name "Net-(D16-PadA)") (class "Default")
      (node (ref "D16") (pin "A") (pinfunction "A_A") (pintype "passive"))
      (node (ref "R13") (pin "1") (pinfunction "1_1") (pintype "passive"))
    )
    (net (code "28") (name "Net-(D17-PadA)") (class "Default")
      (node (ref "D17") (pin "A") (pinfunction "A_A") (pintype "passive"))
      (node (ref "R20") (pin "1") (pinfunction "1_1") (pintype "passive"))
    )
    (net (code "29") (name "Net-(J4-SIGNAL)") (class "Default")
      (node (ref "C16") (pin "1") (pinfunction "1_1") (pintype "passive"))
      (node (ref "J4") (pin "FEED") (pinfunction "SIGNAL_FEED") (pintype "bidirectional"))
      (node (ref "R4") (pin "1") (pinfunction "1_1") (pintype "passive"))
    )
    (net (code "30") (name "Net-(LS2-PadP)") (class "Default")
      (node (ref "LS2") (pin "P") (pinfunction "P_P") (pintype "passive"))
      (node (ref "R32") (pin "2") (pinfunction "2_2") (pintype "passive"))
    )
    (net (code "31") (name "Net-(POWER-Pad1)") (class "Default")
      (node (ref "POWER") (pin "1") (pinfunction "1_1") (pintype "passive"))
      (node (ref "SW2") (pin "2") (pinfunction "2_2") (pintype "passive"))
    )
    (net (code "32") (name "Net-(U13-1PPS)") (class "Default")
      (node (ref "R14") (pin "2") (pinfunction "2_2") (pintype "passive"))
      (node (ref "U13") (pin "6") (pinfunction "1PPS_6") (pintype "output"))
    )
    (net (code "33") (name "Net-(U13-AADET_N)") (class "Default")
      (node (ref "R13") (pin "2") (pinfunction "2_2") (pintype "passive"))
      (node (ref "U13") (pin "8") (pinfunction "AADET_N_8") (pintype "output"))
    )
    (net (code "34") (name "Net-(U13-FORCE_ON)") (class "Default")
      (node (ref "R11") (pin "2") (pinfunction "2_2") (pintype "passive"))
      (node (ref "R12") (pin "2") (pinfunction "2_2") (pintype "passive"))
      (node (ref "U13") (pin "7") (pinfunction "FORCE_ON_7") (pintype "input"))
    )
    (net (code "35") (name "Net-(U13-~{RESET})") (class "Default")
      (node (ref "R17") (pin "1") (pinfunction "1_1") (pintype "passive"))
      (node (ref "U13") (pin "10") (pinfunction "~{RESET}_10") (pintype "input"))
    )
    (net (code "36") (name "Net-(U15-VOUT)") (class "Default")
      (node (ref "C12") (pin "1") (pinfunction "1_1") (pintype "passive"))
      (node (ref "C3") (pin "+") (pinfunction "+_+") (pintype "passive"))
      (node (ref "F2") (pin "1") (pinfunction "1_1") (pintype "bidirectional"))
      (node (ref "U15") (pin "2") (pinfunction "VOUT_2") (pintype "output"))
    )
    (net (code "37") (name "Net-(U16-VOUT)") (class "Default")
      (node (ref "C10") (pin "1") (pinfunction "1_1") (pintype "passive"))
      (node (ref "C5") (pin "+") (pinfunction "+_+") (pintype "passive"))
      (node (ref "F4") (pin "1") (pinfunction "1_1") (pintype "bidirectional"))
      (node (ref "U16") (pin "2") (pinfunction "VOUT_2") (pintype "output"))
    )
    (net (code "38") (name "Net-(X1-ANT)") (class "Default")
      (node (ref "U14") (pin "ANT") (pinfunction "ANT_ANT") (pintype "bidirectional"))
      (node (ref "X1") (pin "ANTENNA") (pinfunction "ANT_ANTENNA") (pintype "bidirectional"))
    )
    (net (code "39") (name "OSC_IN") (class "Default")
      (node (ref "C15") (pin "2") (pinfunction "2_2") (pintype "passive"))
      (node (ref "U2") (pin "5") (pinfunction "OSC_IN_5") (pintype "input"))
      (node (ref "Y1") (pin "1") (pinfunction "1_1") (pintype "passive"))
    )
    (net (code "40") (name "OSC_OUT") (class "Default")
      (node (ref "C14") (pin "2") (pinfunction "2_2") (pintype "passive"))
      (node (ref "U2") (pin "6") (pinfunction "OSC_OUT_6") (pintype "output"))
      (node (ref "Y1") (pin "3") (pinfunction "3_3") (pintype "passive"))
    )
    (net (code "41") (name "RX1") (class "Default")
      (node (ref "U13") (pin "2") (pinfunction "TXD1_2") (pintype "output"))
      (node (ref "U2") (pin "31") (pinfunction "PA10_31") (pintype "bidirectional"))
    )
    (net (code "42") (name "RX2") (class "Default")
      (node (ref "U14") (pin "TX") (pinfunction "TXD_TX") (pintype "bidirectional"))
      (node (ref "U2") (pin "13") (pinfunction "PA3_13") (pintype "bidirectional"))
    )
    (net (code "43") (name "RX3") (class "Default")
      (node (ref "U2") (pin "22") (pinfunction "PB11_22") (pintype "bidirectional"))
      (node (ref "X2") (pin "3") (pinfunction "S_3") (pintype "passive"))
    )
    (net (code "44") (name "SCK") (class "Default")
      (node (ref "J2") (pin "5") (pinfunction "CLK(SCK)_5") (pintype "bidirectional"))
      (node (ref "U2") (pin "26") (pinfunction "PB13_26") (pintype "bidirectional"))
    )
    (net (code "45") (name "SCL") (class "Default")
      (node (ref "J3") (pin "3") (pinfunction "3_3") (pintype "passive"))
      (node (ref "U2") (pin "42") (pinfunction "PB6_42") (pintype "bidirectional"))
    )
    (net (code "46") (name "SDA") (class "Default")
      (node (ref "J3") (pin "2") (pinfunction "2_2") (pintype "passive"))
      (node (ref "U2") (pin "43") (pinfunction "PB7_43") (pintype "bidirectional"))
    )
    (net (code "47") (name "SWCLK") (class "Default")
      (node (ref "STM1") (pin "2") (pinfunction "2_2") (pintype "passive"))
      (node (ref "U2") (pin "37") (pinfunction "PA14_37") (pintype "bidirectional"))
    )
    (net (code "48") (name "SWDIO") (class "Default")
      (node (ref "STM1") (pin "3") (pinfunction "3_3") (pintype "passive"))
      (node (ref "U2") (pin "34") (pinfunction "PA13_34") (pintype "bidirectional"))
    )
    (net (code "49") (name "TX1") (class "Default")
      (node (ref "R15") (pin "1") (pinfunction "1_1") (pintype "passive"))
      (node (ref "U2") (pin "30") (pinfunction "PA9_30") (pintype "bidirectional"))
    )
    (net (code "50") (name "TX2") (class "Default")
      (node (ref "U14") (pin "RX") (pinfunction "RXD_RX") (pintype "bidirectional"))
      (node (ref "U2") (pin "12") (pinfunction "PA2_12") (pintype "bidirectional"))
    )
    (net (code "51") (name "TX3") (class "Default")
      (node (ref "U2") (pin "21") (pinfunction "PB10_21") (pintype "bidirectional"))
      (node (ref "X2") (pin "2") (pinfunction "S_2") (pintype "passive"))
    )
    (net (code "52") (name "TXD") (class "Default")
      (node (ref "R15") (pin "2") (pinfunction "2_2") (pintype "passive"))
      (node (ref "R16") (pin "2") (pinfunction "2_2") (pintype "passive"))
      (node (ref "U13") (pin "1") (pinfunction "RXD1_1") (pintype "input"))
    )
    (net (code "53") (name "USB_N") (class "Default")
      (node (ref "J5") (pin "D-1") (pinfunction "D-_D-1") (pintype "bidirectional"))
      (node (ref "U2") (pin "32") (pinfunction "PA11_32") (pintype "bidirectional"))
    )
    (net (code "54") (name "USB_P") (class "Default")
      (node (ref "J5") (pin "D+1") (pinfunction "D+_D+1") (pintype "bidirectional"))
      (node (ref "U2") (pin "33") (pinfunction "PA12_33") (pintype "bidirectional"))
    )
    (net (code "55") (name "VB") (class "Default")
      (node (ref "U2") (pin "16") (pinfunction "PA6_16") (pintype "bidirectional"))
      (node (ref "VBAT_D") (pin "2") (pinfunction "2_2") (pintype "passive"))
      (node (ref "VBAT_U") (pin "1") (pinfunction "1_1") (pintype "passive"))
    )
    (net (code "56") (name "VCC") (class "Default")
      (node (ref "D10") (pin "2") (pinfunction "A_2") (pintype "passive"))
      (node (ref "D11") (pin "2") (pinfunction "A_2") (pintype "passive"))
      (node (ref "SW2") (pin "1") (pinfunction "1_1") (pintype "passive"))
      (node (ref "VBAT_U") (pin "2") (pinfunction "2_2") (pintype "passive"))
    )
    (net (code "57") (name "VDDA") (class "Default")
      (node (ref "L2") (pin "2") (pinfunction "2_2") (pintype "passive"))
      (node (ref "U2") (pin "9") (pinfunction "VDDA_9") (pintype "power_in"))
      (node (ref "VDDA3") (pin "1") (pinfunction "1_1") (pintype "passive"))
      (node (ref "VDDA4") (pin "1") (pinfunction "1_1") (pintype "passive"))
    )
    (net (code "58") (name "V_BCKP") (class "Default")
      (node (ref "B1") (pin "+") (pinfunction "+_+") (pintype "power_in"))
      (node (ref "C24") (pin "1") (pinfunction "1_1") (pintype "passive"))
      (node (ref "C26") (pin "+") (pinfunction "+_+") (pintype "passive"))
      (node (ref "R39") (pin "1") (pinfunction "1_1") (pintype "passive"))
      (node (ref "U13") (pin "5") (pinfunction "V_BCKP_5") (pintype "power_in"))
    )
    (net (code "59") (name "XANT") (class "Default")
      (node (ref "C17") (pin "1") (pinfunction "1_1") (pintype "passive"))
      (node (ref "R4") (pin "2") (pinfunction "2_2") (pintype "passive"))
      (node (ref "U13") (pin "11") (pinfunction "EX_ANT_11") (pintype "input"))
    )
    (net (code "60") (name "unconnected-(J2B-DAT1(RSV)-Pad8)") (class "Default")
      (node (ref "J2") (pin "8") (pinfunction "DAT1(RSV)_8") (pintype "bidirectional"))
    )
    (net (code "61") (name "unconnected-(J2B-DAT2(NC)-Pad1)") (class "Default")
      (node (ref "J2") (pin "1") (pinfunction "DAT2(NC)_1") (pintype "bidirectional"))
    )
    (net (code "62") (name "unconnected-(J5-USBID-PadID1)") (class "Default")
      (node (ref "J5") (pin "ID1") (pinfunction "USBID_ID1") (pintype "bidirectional"))
    )
    (net (code "63") (name "unconnected-(U2A-PA4-Pad14)") (class "Default")
      (node (ref "U2") (pin "14") (pinfunction "PA4_14") (pintype "bidirectional"))
    )
    (net (code "64") (name "unconnected-(U2A-PA15-Pad38)") (class "Default")
      (node (ref "U2") (pin "38") (pinfunction "PA15_38") (pintype "bidirectional"))
    )
    (net (code "65") (name "unconnected-(U2A-PB1-Pad19)") (class "Default")
      (node (ref "U2") (pin "19") (pinfunction "PB1_19") (pintype "bidirectional"))
    )
    (net (code "66") (name "unconnected-(U2A-PB2-Pad20)") (class "Default")
      (node (ref "U2") (pin "20") (pinfunction "PB2_20") (pintype "bidirectional"))
    )
    (net (code "67") (name "unconnected-(U2A-PB3-Pad39)") (class "Default")
      (node (ref "U2") (pin "39") (pinfunction "PB3_39") (pintype "bidirectional"))
    )
    (net (code "68") (name "unconnected-(U2A-PB8-Pad45)") (class "Default")
      (node (ref "U2") (pin "45") (pinfunction "PB8_45") (pintype "bidirectional"))
    )
    (net (code "69") (name "unconnected-(U2A-PB9-Pad46)") (class "Default")
      (node (ref "U2") (pin "46") (pinfunction "PB9_46") (pintype "bidirectional"))
    )
    (net (code "70") (name "unconnected-(U2A-PC13-Pad2)") (class "Default")
      (node (ref "U2") (pin "2") (pinfunction "PC13_2") (pintype "bidirectional"))
    )
    (net (code "71") (name "unconnected-(U2A-PC14-OSC32_IN-Pad3)") (class "Default")
      (node (ref "U2") (pin "3") (pinfunction "PC14-OSC32_IN_3") (pintype "bidirectional"))
    )
    (net (code "72") (name "unconnected-(U2A-PC15-OSC32_OUT-Pad4)") (class "Default")
      (node (ref "U2") (pin "4") (pinfunction "PC15-OSC32_OUT_4") (pintype "bidirectional"))
    )
    (net (code "73") (name "unconnected-(U14-Pad3V3)") (class "Default")
      (node (ref "U14") (pin "3V3") (pinfunction "3V3_3V3") (pintype "bidirectional"))
    )
    (net (code "74") (name "unconnected-(U14-PadPB0)") (class "Default")
      (node (ref "U14") (pin "PB0") (pinfunction "PB0_PB0") (pintype "bidirectional"))
    )
    (net (code "75") (name "unconnected-(U14-PadPB1)") (class "Default")
      (node (ref "U14") (pin "PB1") (pinfunction "PB1_PB1") (pintype "bidirectional"))
    )
    (net (code "76") (name "unconnected-(U14-PadPB3)") (class "Default")
      (node (ref "U14") (pin "PB3") (pinfunction "PB3_PB3") (pintype "bidirectional"))
    )
    (net (code "77") (name "unconnected-(U14-PadRST)") (class "Default")
      (node (ref "U14") (pin "RST") (pinfunction "RST_RST") (pintype "bidirectional"))
    )
    (net (code "78") (name "unconnected-(U14-PadSWIM)") (class "Default")
      (node (ref "U14") (pin "SWIM") (pinfunction "SWIM_SWIM") (pintype "bidirectional"))
    )
  )
)
